# Conn_B.net
KiCad netlist of a schematic drawn in Altium Designer
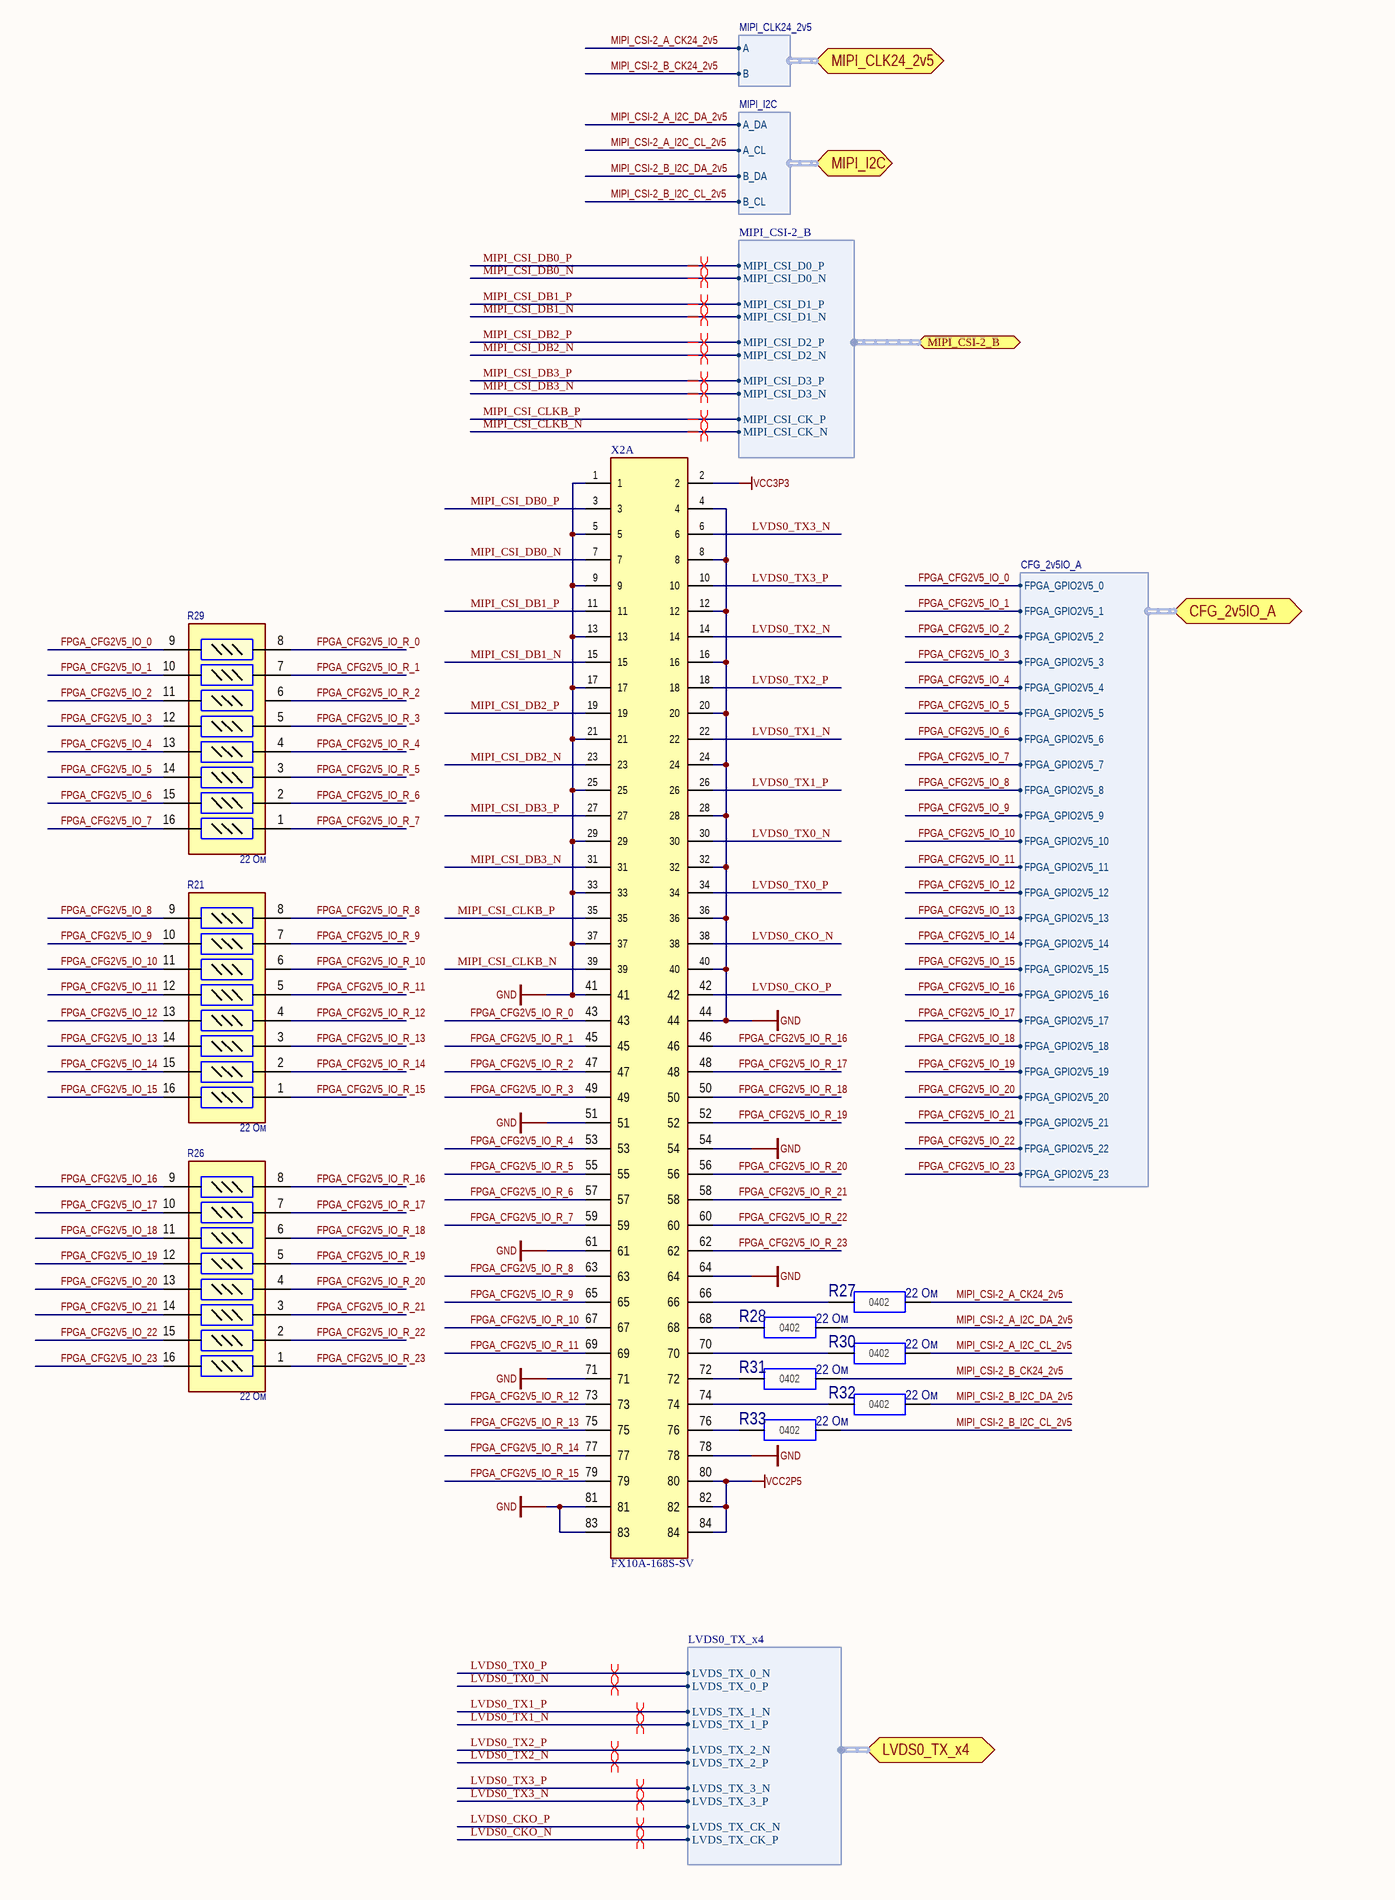
[diagram p0: Conn_B.SchDoc, left]
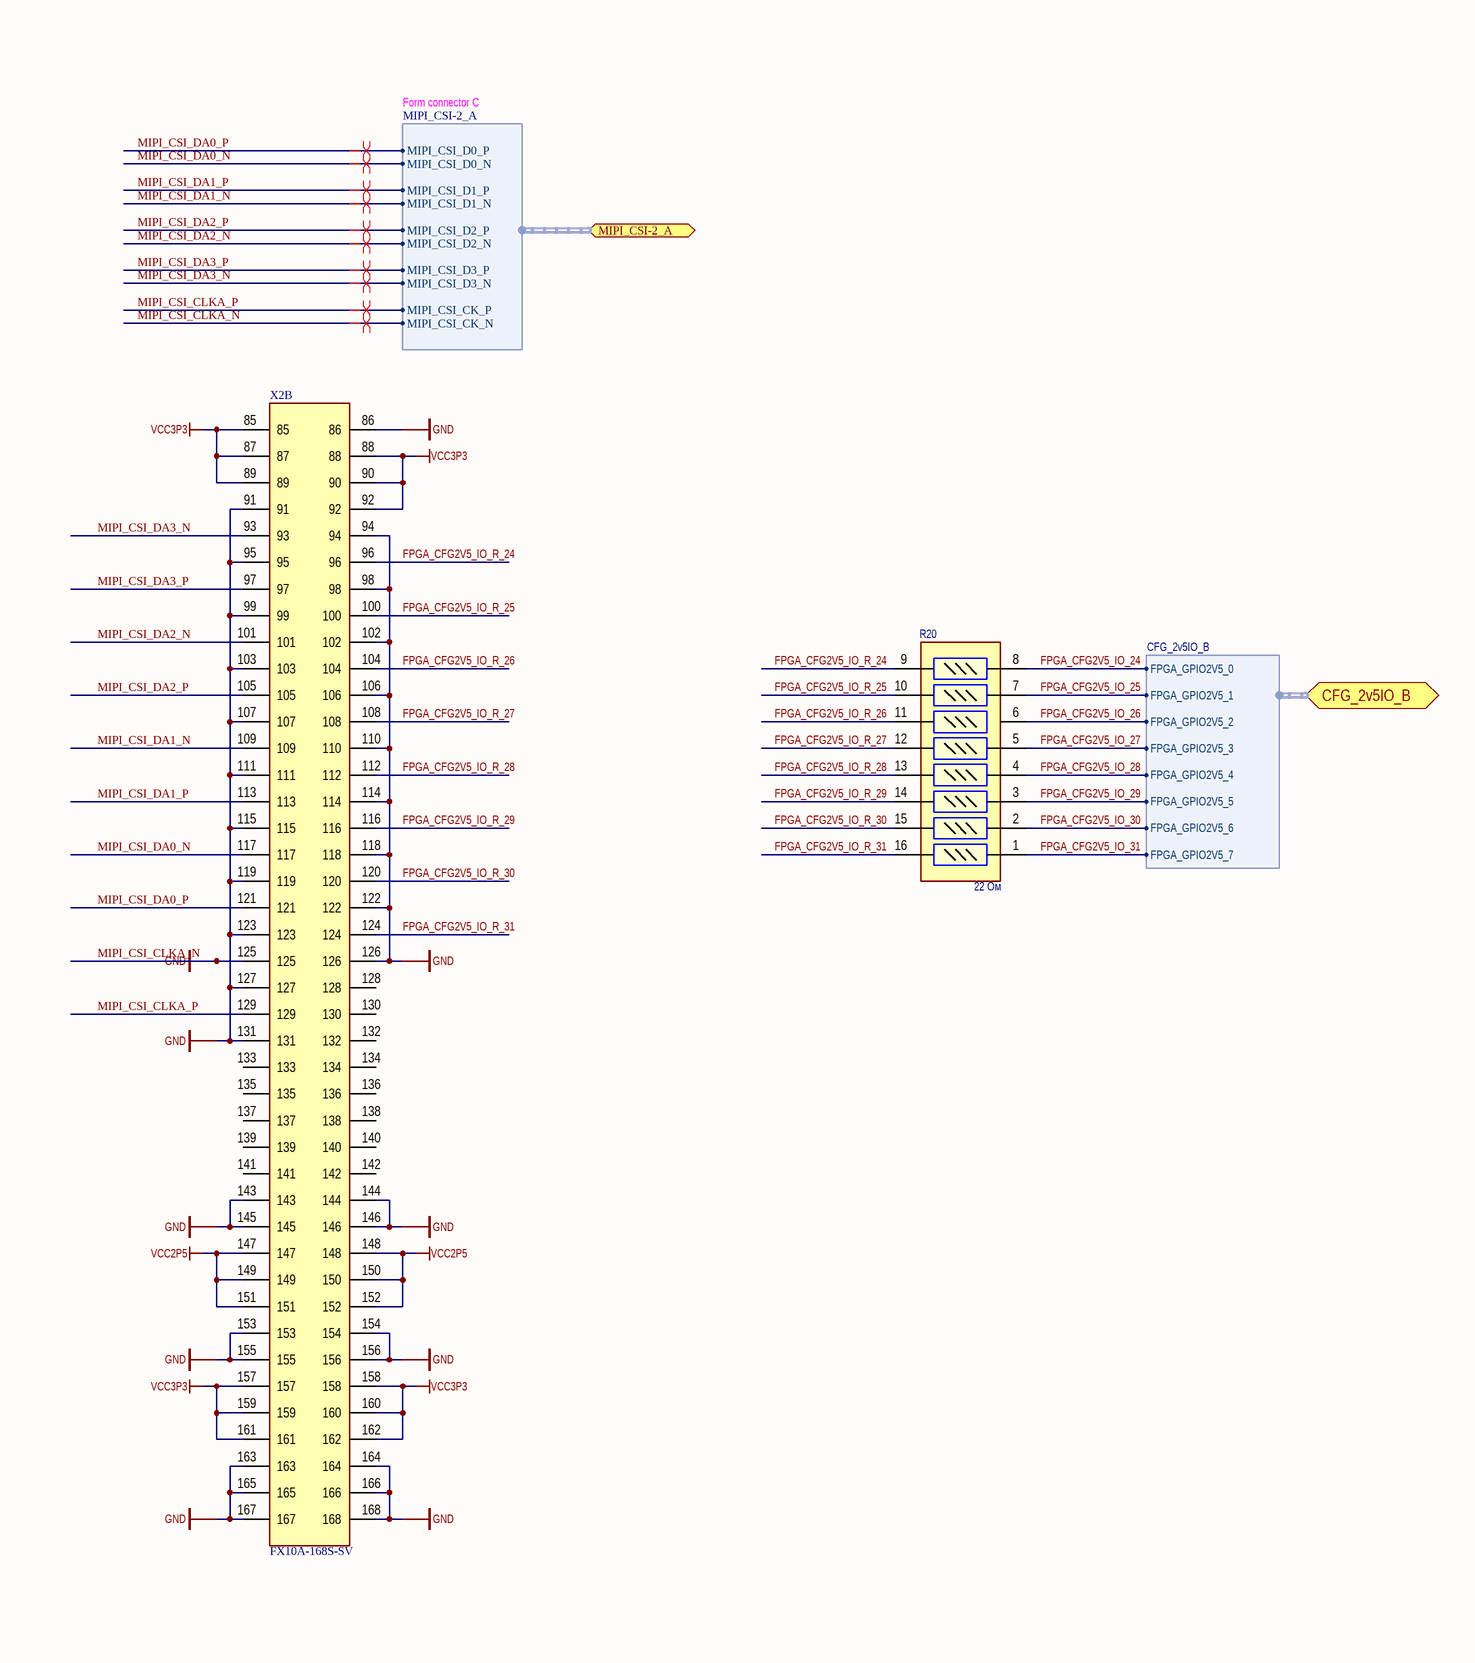
[diagram p1: Conn_B.SchDoc, right]

(export (version "E")
  (design (tool "Eeschema 10.0.6"))
  (components
    (comp (ref "R20")
      (value "22 Ом")
      (footprint "CAT16-J8")
      (description "Набор чип резисторов")
      (fields (field (name "Comment") "YC248-JR-07-22 Ом"))
      (libsource (lib "SD_IC") (part "YC248-JR-07-#"))
    )
    (comp (ref "R21")
      (value "22 Ом")
      (footprint "CAT16-J8")
      (description "Набор чип резисторов")
      (fields (field (name "Comment") "YC248-JR-07-22 Ом"))
      (libsource (lib "SD_IC") (part "YC248-JR-07-#"))
    )
    (comp (ref "R26")
      (value "22 Ом")
      (footprint "CAT16-J8")
      (description "Набор чип резисторов")
      (fields (field (name "Comment") "YC248-JR-07-22 Ом"))
      (libsource (lib "SD_IC") (part "YC248-JR-07-#"))
    )
    (comp (ref "R27")
      (value "22 Ом")
      (footprint "CR0402(1005)")
      (description "Чип резистор")
      (fields (field (name "TOLERANCE") "5%") (field (name "Comment") "CR0402-22 Ом-±5%"))
      (libsource (lib "Чип резисторы") (part "CR0402-#-±5%"))
    )
    (comp (ref "R28")
      (value "22 Ом")
      (footprint "CR0402(1005)")
      (description "Чип резистор")
      (fields (field (name "TOLERANCE") "5%") (field (name "Comment") "CR0402-22 Ом-±5%"))
      (libsource (lib "Чип резисторы") (part "CR0402-#-±5%"))
    )
    (comp (ref "R29")
      (value "22 Ом")
      (footprint "CAT16-J8")
      (description "Набор чип резисторов")
      (fields (field (name "Comment") "YC248-JR-07-22 Ом"))
      (libsource (lib "SD_IC") (part "YC248-JR-07-#"))
    )
    (comp (ref "R30")
      (value "22 Ом")
      (footprint "CR0402(1005)")
      (description "Чип резистор")
      (fields (field (name "TOLERANCE") "5%") (field (name "Comment") "CR0402-22 Ом-±5%"))
      (libsource (lib "Чип резисторы") (part "CR0402-#-±5%"))
    )
    (comp (ref "R31")
      (value "22 Ом")
      (footprint "CR0402(1005)")
      (description "Чип резистор")
      (fields (field (name "TOLERANCE") "5%") (field (name "Comment") "CR0402-22 Ом-±5%"))
      (libsource (lib "Чип резисторы") (part "CR0402-#-±5%"))
    )
    (comp (ref "R32")
      (value "22 Ом")
      (footprint "CR0402(1005)")
      (description "Чип резистор")
      (fields (field (name "TOLERANCE") "5%") (field (name "Comment") "CR0402-22 Ом-±5%"))
      (libsource (lib "Чип резисторы") (part "CR0402-#-±5%"))
    )
    (comp (ref "R33")
      (value "22 Ом")
      (footprint "CR0402(1005)")
      (description "Чип резистор")
      (fields (field (name "TOLERANCE") "5%") (field (name "Comment") "CR0402-22 Ом-±5%"))
      (libsource (lib "Чип резисторы") (part "CR0402-#-±5%"))
    )
    (comp (ref "X2")
      (value "FX10A-168S-SV")
      (footprint "FX10A-168S-SV")
      (libsource (lib "SD_IC") (part "FX10A-168S-SV"))
    )
  )
  (nets
    (net (code "8") (name "/FPGA_CFG2V5_IO_0") (class "Default")
      (node (ref "R29") (pin "9") (pintype "passive"))
    )
    (net (code "9") (name "/FPGA_CFG2V5_IO_1") (class "Default")
      (node (ref "R29") (pin "10") (pintype "passive"))
    )
    (net (code "10") (name "/FPGA_CFG2V5_IO_2") (class "Default")
      (node (ref "R29") (pin "11") (pintype "passive"))
    )
    (net (code "11") (name "/FPGA_CFG2V5_IO_3") (class "Default")
      (node (ref "R29") (pin "12") (pintype "passive"))
    )
    (net (code "12") (name "/FPGA_CFG2V5_IO_4") (class "Default")
      (node (ref "R29") (pin "13") (pintype "passive"))
    )
    (net (code "13") (name "/FPGA_CFG2V5_IO_5") (class "Default")
      (node (ref "R29") (pin "14") (pintype "passive"))
    )
    (net (code "14") (name "/FPGA_CFG2V5_IO_6") (class "Default")
      (node (ref "R29") (pin "15") (pintype "passive"))
    )
    (net (code "15") (name "/FPGA_CFG2V5_IO_7") (class "Default")
      (node (ref "R29") (pin "16") (pintype "passive"))
    )
    (net (code "16") (name "/FPGA_CFG2V5_IO_8") (class "Default")
      (node (ref "R21") (pin "9") (pintype "passive"))
    )
    (net (code "17") (name "/FPGA_CFG2V5_IO_9") (class "Default")
      (node (ref "R21") (pin "10") (pintype "passive"))
    )
    (net (code "18") (name "/FPGA_CFG2V5_IO_10") (class "Default")
      (node (ref "R21") (pin "11") (pintype "passive"))
    )
    (net (code "19") (name "/FPGA_CFG2V5_IO_11") (class "Default")
      (node (ref "R21") (pin "12") (pintype "passive"))
    )
    (net (code "20") (name "/FPGA_CFG2V5_IO_12") (class "Default")
      (node (ref "R21") (pin "13") (pintype "passive"))
    )
    (net (code "21") (name "/FPGA_CFG2V5_IO_13") (class "Default")
      (node (ref "R21") (pin "14") (pintype "passive"))
    )
    (net (code "22") (name "/FPGA_CFG2V5_IO_14") (class "Default")
      (node (ref "R21") (pin "15") (pintype "passive"))
    )
    (net (code "23") (name "/FPGA_CFG2V5_IO_15") (class "Default")
      (node (ref "R21") (pin "16") (pintype "passive"))
    )
    (net (code "24") (name "/FPGA_CFG2V5_IO_16") (class "Default")
      (node (ref "R26") (pin "9") (pintype "passive"))
    )
    (net (code "25") (name "/FPGA_CFG2V5_IO_17") (class "Default")
      (node (ref "R26") (pin "10") (pintype "passive"))
    )
    (net (code "26") (name "/FPGA_CFG2V5_IO_18") (class "Default")
      (node (ref "R26") (pin "11") (pintype "passive"))
    )
    (net (code "27") (name "/FPGA_CFG2V5_IO_19") (class "Default")
      (node (ref "R26") (pin "12") (pintype "passive"))
    )
    (net (code "28") (name "/FPGA_CFG2V5_IO_20") (class "Default")
      (node (ref "R26") (pin "13") (pintype "passive"))
    )
    (net (code "29") (name "/FPGA_CFG2V5_IO_21") (class "Default")
      (node (ref "R26") (pin "14") (pintype "passive"))
    )
    (net (code "30") (name "/FPGA_CFG2V5_IO_22") (class "Default")
      (node (ref "R26") (pin "15") (pintype "passive"))
    )
    (net (code "31") (name "/FPGA_CFG2V5_IO_23") (class "Default")
      (node (ref "R26") (pin "16") (pintype "passive"))
    )
    (net (code "32") (name "/FPGA_CFG2V5_IO_24") (class "Default")
      (node (ref "R20") (pin "8") (pintype "passive"))
    )
    (net (code "33") (name "/FPGA_CFG2V5_IO_25") (class "Default")
      (node (ref "R20") (pin "7") (pintype "passive"))
    )
    (net (code "34") (name "/FPGA_CFG2V5_IO_26") (class "Default")
      (node (ref "R20") (pin "6") (pintype "passive"))
    )
    (net (code "35") (name "/FPGA_CFG2V5_IO_27") (class "Default")
      (node (ref "R20") (pin "5") (pintype "passive"))
    )
    (net (code "36") (name "/FPGA_CFG2V5_IO_28") (class "Default")
      (node (ref "R20") (pin "4") (pintype "passive"))
    )
    (net (code "37") (name "/FPGA_CFG2V5_IO_29") (class "Default")
      (node (ref "R20") (pin "3") (pintype "passive"))
    )
    (net (code "38") (name "/FPGA_CFG2V5_IO_30") (class "Default")
      (node (ref "R20") (pin "2") (pintype "passive"))
    )
    (net (code "39") (name "/FPGA_CFG2V5_IO_31") (class "Default")
      (node (ref "R20") (pin "1") (pintype "passive"))
    )
    (net (code "40") (name "/FPGA_CFG2V5_IO_R_0") (class "Default")
      (node (ref "R29") (pin "8") (pintype "passive"))
      (node (ref "X2") (pin "43") (pinfunction "43_43") (pintype "passive"))
    )
    (net (code "41") (name "/FPGA_CFG2V5_IO_R_1") (class "Default")
      (node (ref "R29") (pin "7") (pintype "passive"))
      (node (ref "X2") (pin "45") (pinfunction "45_45") (pintype "passive"))
    )
    (net (code "42") (name "/FPGA_CFG2V5_IO_R_2") (class "Default")
      (node (ref "R29") (pin "6") (pintype "passive"))
      (node (ref "X2") (pin "47") (pinfunction "47_47") (pintype "passive"))
    )
    (net (code "43") (name "/FPGA_CFG2V5_IO_R_3") (class "Default")
      (node (ref "R29") (pin "5") (pintype "passive"))
      (node (ref "X2") (pin "49") (pinfunction "49_49") (pintype "passive"))
    )
    (net (code "44") (name "/FPGA_CFG2V5_IO_R_4") (class "Default")
      (node (ref "R29") (pin "4") (pintype "passive"))
      (node (ref "X2") (pin "53") (pinfunction "53_53") (pintype "passive"))
    )
    (net (code "45") (name "/FPGA_CFG2V5_IO_R_5") (class "Default")
      (node (ref "R29") (pin "3") (pintype "passive"))
      (node (ref "X2") (pin "55") (pinfunction "55_55") (pintype "passive"))
    )
    (net (code "46") (name "/FPGA_CFG2V5_IO_R_6") (class "Default")
      (node (ref "R29") (pin "2") (pintype "passive"))
      (node (ref "X2") (pin "57") (pinfunction "57_57") (pintype "passive"))
    )
    (net (code "47") (name "/FPGA_CFG2V5_IO_R_7") (class "Default")
      (node (ref "R29") (pin "1") (pintype "passive"))
      (node (ref "X2") (pin "59") (pinfunction "59_59") (pintype "passive"))
    )
    (net (code "48") (name "/FPGA_CFG2V5_IO_R_8") (class "Default")
      (node (ref "R21") (pin "8") (pintype "passive"))
      (node (ref "X2") (pin "63") (pinfunction "63_63") (pintype "passive"))
    )
    (net (code "49") (name "/FPGA_CFG2V5_IO_R_9") (class "Default")
      (node (ref "R21") (pin "7") (pintype "passive"))
      (node (ref "X2") (pin "65") (pinfunction "65_65") (pintype "passive"))
    )
    (net (code "50") (name "/FPGA_CFG2V5_IO_R_10") (class "Default")
      (node (ref "R21") (pin "6") (pintype "passive"))
      (node (ref "X2") (pin "67") (pinfunction "67_67") (pintype "passive"))
    )
    (net (code "51") (name "/FPGA_CFG2V5_IO_R_11") (class "Default")
      (node (ref "R21") (pin "5") (pintype "passive"))
      (node (ref "X2") (pin "69") (pinfunction "69_69") (pintype "passive"))
    )
    (net (code "52") (name "/FPGA_CFG2V5_IO_R_12") (class "Default")
      (node (ref "R21") (pin "4") (pintype "passive"))
      (node (ref "X2") (pin "73") (pinfunction "73_73") (pintype "passive"))
    )
    (net (code "53") (name "/FPGA_CFG2V5_IO_R_13") (class "Default")
      (node (ref "R21") (pin "3") (pintype "passive"))
      (node (ref "X2") (pin "75") (pinfunction "75_75") (pintype "passive"))
    )
    (net (code "54") (name "/FPGA_CFG2V5_IO_R_14") (class "Default")
      (node (ref "R21") (pin "2") (pintype "passive"))
      (node (ref "X2") (pin "77") (pinfunction "77_77") (pintype "passive"))
    )
    (net (code "55") (name "/FPGA_CFG2V5_IO_R_15") (class "Default")
      (node (ref "R21") (pin "1") (pintype "passive"))
      (node (ref "X2") (pin "79") (pinfunction "79_79") (pintype "passive"))
    )
    (net (code "56") (name "/FPGA_CFG2V5_IO_R_16") (class "Default")
      (node (ref "R26") (pin "8") (pintype "passive"))
      (node (ref "X2") (pin "46") (pinfunction "46_46") (pintype "passive"))
    )
    (net (code "57") (name "/FPGA_CFG2V5_IO_R_17") (class "Default")
      (node (ref "R26") (pin "7") (pintype "passive"))
      (node (ref "X2") (pin "48") (pinfunction "48_48") (pintype "passive"))
    )
    (net (code "58") (name "/FPGA_CFG2V5_IO_R_18") (class "Default")
      (node (ref "R26") (pin "6") (pintype "passive"))
      (node (ref "X2") (pin "50") (pinfunction "50_50") (pintype "passive"))
    )
    (net (code "59") (name "/FPGA_CFG2V5_IO_R_19") (class "Default")
      (node (ref "R26") (pin "5") (pintype "passive"))
      (node (ref "X2") (pin "52") (pinfunction "52_52") (pintype "passive"))
    )
    (net (code "60") (name "/FPGA_CFG2V5_IO_R_20") (class "Default")
      (node (ref "R26") (pin "4") (pintype "passive"))
      (node (ref "X2") (pin "56") (pinfunction "56_56") (pintype "passive"))
    )
    (net (code "61") (name "/FPGA_CFG2V5_IO_R_21") (class "Default")
      (node (ref "R26") (pin "3") (pintype "passive"))
      (node (ref "X2") (pin "58") (pinfunction "58_58") (pintype "passive"))
    )
    (net (code "62") (name "/FPGA_CFG2V5_IO_R_22") (class "Default")
      (node (ref "R26") (pin "2") (pintype "passive"))
      (node (ref "X2") (pin "60") (pinfunction "60_60") (pintype "passive"))
    )
    (net (code "63") (name "/FPGA_CFG2V5_IO_R_23") (class "Default")
      (node (ref "R26") (pin "1") (pintype "passive"))
      (node (ref "X2") (pin "62") (pinfunction "62_62") (pintype "passive"))
    )
    (net (code "64") (name "/FPGA_CFG2V5_IO_R_24") (class "Default")
      (node (ref "R20") (pin "9") (pintype "passive"))
      (node (ref "X2") (pin "96") (pinfunction "96_96") (pintype "passive"))
    )
    (net (code "65") (name "/FPGA_CFG2V5_IO_R_25") (class "Default")
      (node (ref "R20") (pin "10") (pintype "passive"))
      (node (ref "X2") (pin "100") (pinfunction "100_100") (pintype "passive"))
    )
    (net (code "66") (name "/FPGA_CFG2V5_IO_R_26") (class "Default")
      (node (ref "R20") (pin "11") (pintype "passive"))
      (node (ref "X2") (pin "104") (pinfunction "104_104") (pintype "passive"))
    )
    (net (code "67") (name "/FPGA_CFG2V5_IO_R_27") (class "Default")
      (node (ref "R20") (pin "12") (pintype "passive"))
      (node (ref "X2") (pin "108") (pinfunction "108_108") (pintype "passive"))
    )
    (net (code "68") (name "/FPGA_CFG2V5_IO_R_28") (class "Default")
      (node (ref "R20") (pin "13") (pintype "passive"))
      (node (ref "X2") (pin "112") (pinfunction "112_112") (pintype "passive"))
    )
    (net (code "69") (name "/FPGA_CFG2V5_IO_R_29") (class "Default")
      (node (ref "R20") (pin "14") (pintype "passive"))
      (node (ref "X2") (pin "116") (pinfunction "116_116") (pintype "passive"))
    )
    (net (code "70") (name "/FPGA_CFG2V5_IO_R_30") (class "Default")
      (node (ref "R20") (pin "15") (pintype "passive"))
      (node (ref "X2") (pin "120") (pinfunction "120_120") (pintype "passive"))
    )
    (net (code "71") (name "/FPGA_CFG2V5_IO_R_31") (class "Default")
      (node (ref "R20") (pin "16") (pintype "passive"))
      (node (ref "X2") (pin "124") (pinfunction "124_124") (pintype "passive"))
    )
    (net (code "72") (name "/LVDS0_CKO_N") (class "Default")
      (node (ref "X2") (pin "38") (pinfunction "38_38") (pintype "passive"))
    )
    (net (code "73") (name "/LVDS0_CKO_P") (class "Default")
      (node (ref "X2") (pin "42") (pinfunction "42_42") (pintype "passive"))
    )
    (net (code "74") (name "/LVDS0_TX0_N") (class "Default")
      (node (ref "X2") (pin "30") (pinfunction "30_30") (pintype "passive"))
    )
    (net (code "75") (name "/LVDS0_TX0_P") (class "Default")
      (node (ref "X2") (pin "34") (pinfunction "34_34") (pintype "passive"))
    )
    (net (code "76") (name "/LVDS0_TX1_N") (class "Default")
      (node (ref "X2") (pin "22") (pinfunction "22_22") (pintype "passive"))
    )
    (net (code "77") (name "/LVDS0_TX1_P") (class "Default")
      (node (ref "X2") (pin "26") (pinfunction "26_26") (pintype "passive"))
    )
    (net (code "78") (name "/LVDS0_TX2_N") (class "Default")
      (node (ref "X2") (pin "14") (pinfunction "14_14") (pintype "passive"))
    )
    (net (code "79") (name "/LVDS0_TX2_P") (class "Default")
      (node (ref "X2") (pin "18") (pinfunction "18_18") (pintype "passive"))
    )
    (net (code "80") (name "/LVDS0_TX3_N") (class "Default")
      (node (ref "X2") (pin "6") (pinfunction "6_6") (pintype "passive"))
    )
    (net (code "81") (name "/LVDS0_TX3_P") (class "Default")
      (node (ref "X2") (pin "10") (pinfunction "10_10") (pintype "passive"))
    )
    (net (code "82") (name "/MIPI_CSI-2_A_CK24_2v5") (class "Default")
      (node (ref "R27") (pin "2") (pinfunction "-_2") (pintype "passive"))
    )
    (net (code "83") (name "/MIPI_CSI-2_A_I2C_CL_2v5") (class "Default")
      (node (ref "R30") (pin "2") (pinfunction "-_2") (pintype "passive"))
    )
    (net (code "84") (name "/MIPI_CSI-2_A_I2C_DA_2v5") (class "Default")
      (node (ref "R28") (pin "2") (pinfunction "-_2") (pintype "passive"))
    )
    (net (code "85") (name "/MIPI_CSI-2_B_CK24_2v5") (class "Default")
      (node (ref "R31") (pin "2") (pinfunction "-_2") (pintype "passive"))
    )
    (net (code "86") (name "/MIPI_CSI-2_B_I2C_CL_2v5") (class "Default")
      (node (ref "R33") (pin "2") (pinfunction "-_2") (pintype "passive"))
    )
    (net (code "87") (name "/MIPI_CSI-2_B_I2C_DA_2v5") (class "Default")
      (node (ref "R32") (pin "2") (pinfunction "-_2") (pintype "passive"))
    )
    (net (code "88") (name "/MIPI_CSI_CLKA_P") (class "Default")
      (node (ref "X2") (pin "129") (pinfunction "129_129") (pintype "passive"))
    )
    (net (code "89") (name "/MIPI_CSI_CLKB_N") (class "Default")
      (node (ref "X2") (pin "39") (pinfunction "39_39") (pintype "passive"))
    )
    (net (code "90") (name "/MIPI_CSI_CLKB_P") (class "Default")
      (node (ref "X2") (pin "35") (pinfunction "35_35") (pintype "passive"))
    )
    (net (code "91") (name "/MIPI_CSI_DA0_N") (class "Default")
      (node (ref "X2") (pin "117") (pinfunction "117_117") (pintype "passive"))
    )
    (net (code "92") (name "/MIPI_CSI_DA0_P") (class "Default")
      (node (ref "X2") (pin "121") (pinfunction "121_121") (pintype "passive"))
    )
    (net (code "93") (name "/MIPI_CSI_DA1_N") (class "Default")
      (node (ref "X2") (pin "109") (pinfunction "109_109") (pintype "passive"))
    )
    (net (code "94") (name "/MIPI_CSI_DA1_P") (class "Default")
      (node (ref "X2") (pin "113") (pinfunction "113_113") (pintype "passive"))
    )
    (net (code "95") (name "/MIPI_CSI_DA2_N") (class "Default")
      (node (ref "X2") (pin "101") (pinfunction "101_101") (pintype "passive"))
    )
    (net (code "96") (name "/MIPI_CSI_DA2_P") (class "Default")
      (node (ref "X2") (pin "105") (pinfunction "105_105") (pintype "passive"))
    )
    (net (code "97") (name "/MIPI_CSI_DA3_N") (class "Default")
      (node (ref "X2") (pin "93") (pinfunction "93_93") (pintype "passive"))
    )
    (net (code "98") (name "/MIPI_CSI_DA3_P") (class "Default")
      (node (ref "X2") (pin "97") (pinfunction "97_97") (pintype "passive"))
    )
    (net (code "99") (name "/MIPI_CSI_DB0_N") (class "Default")
      (node (ref "X2") (pin "7") (pinfunction "7_7") (pintype "passive"))
    )
    (net (code "100") (name "/MIPI_CSI_DB0_P") (class "Default")
      (node (ref "X2") (pin "3") (pinfunction "3_3") (pintype "passive"))
    )
    (net (code "101") (name "/MIPI_CSI_DB1_N") (class "Default")
      (node (ref "X2") (pin "15") (pinfunction "15_15") (pintype "passive"))
    )
    (net (code "102") (name "/MIPI_CSI_DB1_P") (class "Default")
      (node (ref "X2") (pin "11") (pinfunction "11_11") (pintype "passive"))
    )
    (net (code "103") (name "/MIPI_CSI_DB2_N") (class "Default")
      (node (ref "X2") (pin "23") (pinfunction "23_23") (pintype "passive"))
    )
    (net (code "104") (name "/MIPI_CSI_DB2_P") (class "Default")
      (node (ref "X2") (pin "19") (pinfunction "19_19") (pintype "passive"))
    )
    (net (code "105") (name "/MIPI_CSI_DB3_N") (class "Default")
      (node (ref "X2") (pin "31") (pinfunction "31_31") (pintype "passive"))
    )
    (net (code "106") (name "/MIPI_CSI_DB3_P") (class "Default")
      (node (ref "X2") (pin "27") (pinfunction "27_27") (pintype "passive"))
    )
    (net (code "114") (name "GND") (class "Default")
      (node (ref "X2") (pin "1") (pinfunction "1_1") (pintype "passive"))
      (node (ref "X2") (pin "102") (pinfunction "102_102") (pintype "passive"))
      (node (ref "X2") (pin "103") (pinfunction "103_103") (pintype "passive"))
      (node (ref "X2") (pin "106") (pinfunction "106_106") (pintype "passive"))
      (node (ref "X2") (pin "107") (pinfunction "107_107") (pintype "passive"))
      (node (ref "X2") (pin "110") (pinfunction "110_110") (pintype "passive"))
      (node (ref "X2") (pin "111") (pinfunction "111_111") (pintype "passive"))
      (node (ref "X2") (pin "114") (pinfunction "114_114") (pintype "passive"))
      (node (ref "X2") (pin "115") (pinfunction "115_115") (pintype "passive"))
      (node (ref "X2") (pin "118") (pinfunction "118_118") (pintype "passive"))
      (node (ref "X2") (pin "119") (pinfunction "119_119") (pintype "passive"))
      (node (ref "X2") (pin "12") (pinfunction "12_12") (pintype "passive"))
      (node (ref "X2") (pin "122") (pinfunction "122_122") (pintype "passive"))
      (node (ref "X2") (pin "123") (pinfunction "123_123") (pintype "passive"))
      (node (ref "X2") (pin "125") (pinfunction "125_125") (pintype "passive"))
      (node (ref "X2") (pin "126") (pinfunction "126_126") (pintype "passive"))
      (node (ref "X2") (pin "127") (pinfunction "127_127") (pintype "passive"))
      (node (ref "X2") (pin "13") (pinfunction "13_13") (pintype "passive"))
      (node (ref "X2") (pin "131") (pinfunction "131_131") (pintype "passive"))
      (node (ref "X2") (pin "143") (pinfunction "143_143") (pintype "passive"))
      (node (ref "X2") (pin "144") (pinfunction "144_144") (pintype "passive"))
      (node (ref "X2") (pin "145") (pinfunction "145_145") (pintype "passive"))
      (node (ref "X2") (pin "146") (pinfunction "146_146") (pintype "passive"))
      (node (ref "X2") (pin "153") (pinfunction "153_153") (pintype "passive"))
      (node (ref "X2") (pin "154") (pinfunction "154_154") (pintype "passive"))
      (node (ref "X2") (pin "155") (pinfunction "155_155") (pintype "passive"))
      (node (ref "X2") (pin "156") (pinfunction "156_156") (pintype "passive"))
      (node (ref "X2") (pin "16") (pinfunction "16_16") (pintype "passive"))
      (node (ref "X2") (pin "163") (pinfunction "163_163") (pintype "passive"))
      (node (ref "X2") (pin "164") (pinfunction "164_164") (pintype "passive"))
      (node (ref "X2") (pin "165") (pinfunction "165_165") (pintype "passive"))
      (node (ref "X2") (pin "166") (pinfunction "166_166") (pintype "passive"))
      (node (ref "X2") (pin "167") (pinfunction "167_167") (pintype "passive"))
      (node (ref "X2") (pin "168") (pinfunction "168_168") (pintype "passive"))
      (node (ref "X2") (pin "17") (pinfunction "17_17") (pintype "passive"))
      (node (ref "X2") (pin "20") (pinfunction "20_20") (pintype "passive"))
      (node (ref "X2") (pin "21") (pinfunction "21_21") (pintype "passive"))
      (node (ref "X2") (pin "24") (pinfunction "24_24") (pintype "passive"))
      (node (ref "X2") (pin "25") (pinfunction "25_25") (pintype "passive"))
      (node (ref "X2") (pin "28") (pinfunction "28_28") (pintype "passive"))
      (node (ref "X2") (pin "29") (pinfunction "29_29") (pintype "passive"))
      (node (ref "X2") (pin "32") (pinfunction "32_32") (pintype "passive"))
      (node (ref "X2") (pin "33") (pinfunction "33_33") (pintype "passive"))
      (node (ref "X2") (pin "36") (pinfunction "36_36") (pintype "passive"))
      (node (ref "X2") (pin "37") (pinfunction "37_37") (pintype "passive"))
      (node (ref "X2") (pin "4") (pinfunction "4_4") (pintype "passive"))
      (node (ref "X2") (pin "40") (pinfunction "40_40") (pintype "passive"))
      (node (ref "X2") (pin "41") (pinfunction "41_41") (pintype "passive"))
      (node (ref "X2") (pin "44") (pinfunction "44_44") (pintype "passive"))
      (node (ref "X2") (pin "5") (pinfunction "5_5") (pintype "passive"))
      (node (ref "X2") (pin "51") (pinfunction "51_51") (pintype "passive"))
      (node (ref "X2") (pin "54") (pinfunction "54_54") (pintype "passive"))
      (node (ref "X2") (pin "61") (pinfunction "61_61") (pintype "passive"))
      (node (ref "X2") (pin "64") (pinfunction "64_64") (pintype "passive"))
      (node (ref "X2") (pin "71") (pinfunction "71_71") (pintype "passive"))
      (node (ref "X2") (pin "78") (pinfunction "78_78") (pintype "passive"))
      (node (ref "X2") (pin "8") (pinfunction "8_8") (pintype "passive"))
      (node (ref "X2") (pin "81") (pinfunction "81_81") (pintype "passive"))
      (node (ref "X2") (pin "83") (pinfunction "83_83") (pintype "passive"))
      (node (ref "X2") (pin "86") (pinfunction "86_86") (pintype "passive"))
      (node (ref "X2") (pin "9") (pinfunction "9_9") (pintype "passive"))
      (node (ref "X2") (pin "91") (pinfunction "91_91") (pintype "passive"))
      (node (ref "X2") (pin "94") (pinfunction "94_94") (pintype "passive"))
      (node (ref "X2") (pin "95") (pinfunction "95_95") (pintype "passive"))
      (node (ref "X2") (pin "98") (pinfunction "98_98") (pintype "passive"))
      (node (ref "X2") (pin "99") (pinfunction "99_99") (pintype "passive"))
    )
    (net (code "115") (name "Net-(R27-+)") (class "Default")
      (node (ref "R27") (pin "1") (pinfunction "+_1") (pintype "passive"))
      (node (ref "X2") (pin "66") (pinfunction "66_66") (pintype "passive"))
    )
    (net (code "116") (name "Net-(R28-+)") (class "Default")
      (node (ref "R28") (pin "1") (pinfunction "+_1") (pintype "passive"))
      (node (ref "X2") (pin "68") (pinfunction "68_68") (pintype "passive"))
    )
    (net (code "117") (name "Net-(R30-+)") (class "Default")
      (node (ref "R30") (pin "1") (pinfunction "+_1") (pintype "passive"))
      (node (ref "X2") (pin "70") (pinfunction "70_70") (pintype "passive"))
    )
    (net (code "118") (name "Net-(R31-+)") (class "Default")
      (node (ref "R31") (pin "1") (pinfunction "+_1") (pintype "passive"))
      (node (ref "X2") (pin "72") (pinfunction "72_72") (pintype "passive"))
    )
    (net (code "119") (name "Net-(R32-+)") (class "Default")
      (node (ref "R32") (pin "1") (pinfunction "+_1") (pintype "passive"))
      (node (ref "X2") (pin "74") (pinfunction "74_74") (pintype "passive"))
    )
    (net (code "120") (name "Net-(R33-+)") (class "Default")
      (node (ref "R33") (pin "1") (pinfunction "+_1") (pintype "passive"))
      (node (ref "X2") (pin "76") (pinfunction "76_76") (pintype "passive"))
    )
    (net (code "121") (name "VCC2P5") (class "Default")
      (node (ref "X2") (pin "147") (pinfunction "147_147") (pintype "passive"))
      (node (ref "X2") (pin "148") (pinfunction "148_148") (pintype "passive"))
      (node (ref "X2") (pin "149") (pinfunction "149_149") (pintype "passive"))
      (node (ref "X2") (pin "150") (pinfunction "150_150") (pintype "passive"))
      (node (ref "X2") (pin "151") (pinfunction "151_151") (pintype "passive"))
      (node (ref "X2") (pin "152") (pinfunction "152_152") (pintype "passive"))
      (node (ref "X2") (pin "80") (pinfunction "80_80") (pintype "passive"))
      (node (ref "X2") (pin "82") (pinfunction "82_82") (pintype "passive"))
      (node (ref "X2") (pin "84") (pinfunction "84_84") (pintype "passive"))
    )
    (net (code "122") (name "VCC3P3") (class "Default")
      (node (ref "X2") (pin "157") (pinfunction "157_157") (pintype "passive"))
      (node (ref "X2") (pin "158") (pinfunction "158_158") (pintype "passive"))
      (node (ref "X2") (pin "159") (pinfunction "159_159") (pintype "passive"))
      (node (ref "X2") (pin "160") (pinfunction "160_160") (pintype "passive"))
      (node (ref "X2") (pin "161") (pinfunction "161_161") (pintype "passive"))
      (node (ref "X2") (pin "162") (pinfunction "162_162") (pintype "passive"))
      (node (ref "X2") (pin "2") (pinfunction "2_2") (pintype "passive"))
      (node (ref "X2") (pin "85") (pinfunction "85_85") (pintype "passive"))
      (node (ref "X2") (pin "87") (pinfunction "87_87") (pintype "passive"))
      (node (ref "X2") (pin "88") (pinfunction "88_88") (pintype "passive"))
      (node (ref "X2") (pin "89") (pinfunction "89_89") (pintype "passive"))
      (node (ref "X2") (pin "90") (pinfunction "90_90") (pintype "passive"))
      (node (ref "X2") (pin "92") (pinfunction "92_92") (pintype "passive"))
    )
    (net (code "123") (name "unconnected-(X2-Pad128)") (class "Default")
      (node (ref "X2") (pin "128") (pinfunction "128_128") (pintype "passive"))
    )
    (net (code "124") (name "unconnected-(X2-Pad130)") (class "Default")
      (node (ref "X2") (pin "130") (pinfunction "130_130") (pintype "passive"))
    )
    (net (code "125") (name "unconnected-(X2-Pad132)") (class "Default")
      (node (ref "X2") (pin "132") (pinfunction "132_132") (pintype "passive"))
    )
    (net (code "126") (name "unconnected-(X2-Pad133)") (class "Default")
      (node (ref "X2") (pin "133") (pinfunction "133_133") (pintype "passive"))
    )
    (net (code "127") (name "unconnected-(X2-Pad134)") (class "Default")
      (node (ref "X2") (pin "134") (pinfunction "134_134") (pintype "passive"))
    )
    (net (code "128") (name "unconnected-(X2-Pad135)") (class "Default")
      (node (ref "X2") (pin "135") (pinfunction "135_135") (pintype "passive"))
    )
    (net (code "129") (name "unconnected-(X2-Pad136)") (class "Default")
      (node (ref "X2") (pin "136") (pinfunction "136_136") (pintype "passive"))
    )
    (net (code "130") (name "unconnected-(X2-Pad137)") (class "Default")
      (node (ref "X2") (pin "137") (pinfunction "137_137") (pintype "passive"))
    )
    (net (code "131") (name "unconnected-(X2-Pad138)") (class "Default")
      (node (ref "X2") (pin "138") (pinfunction "138_138") (pintype "passive"))
    )
    (net (code "132") (name "unconnected-(X2-Pad139)") (class "Default")
      (node (ref "X2") (pin "139") (pinfunction "139_139") (pintype "passive"))
    )
    (net (code "133") (name "unconnected-(X2-Pad140)") (class "Default")
      (node (ref "X2") (pin "140") (pinfunction "140_140") (pintype "passive"))
    )
    (net (code "134") (name "unconnected-(X2-Pad141)") (class "Default")
      (node (ref "X2") (pin "141") (pinfunction "141_141") (pintype "passive"))
    )
    (net (code "135") (name "unconnected-(X2-Pad142)") (class "Default")
      (node (ref "X2") (pin "142") (pinfunction "142_142") (pintype "passive"))
    )
  )
)
